# schema_v2_2.net
KiCad netlist of a schematic drawn in EAGLE
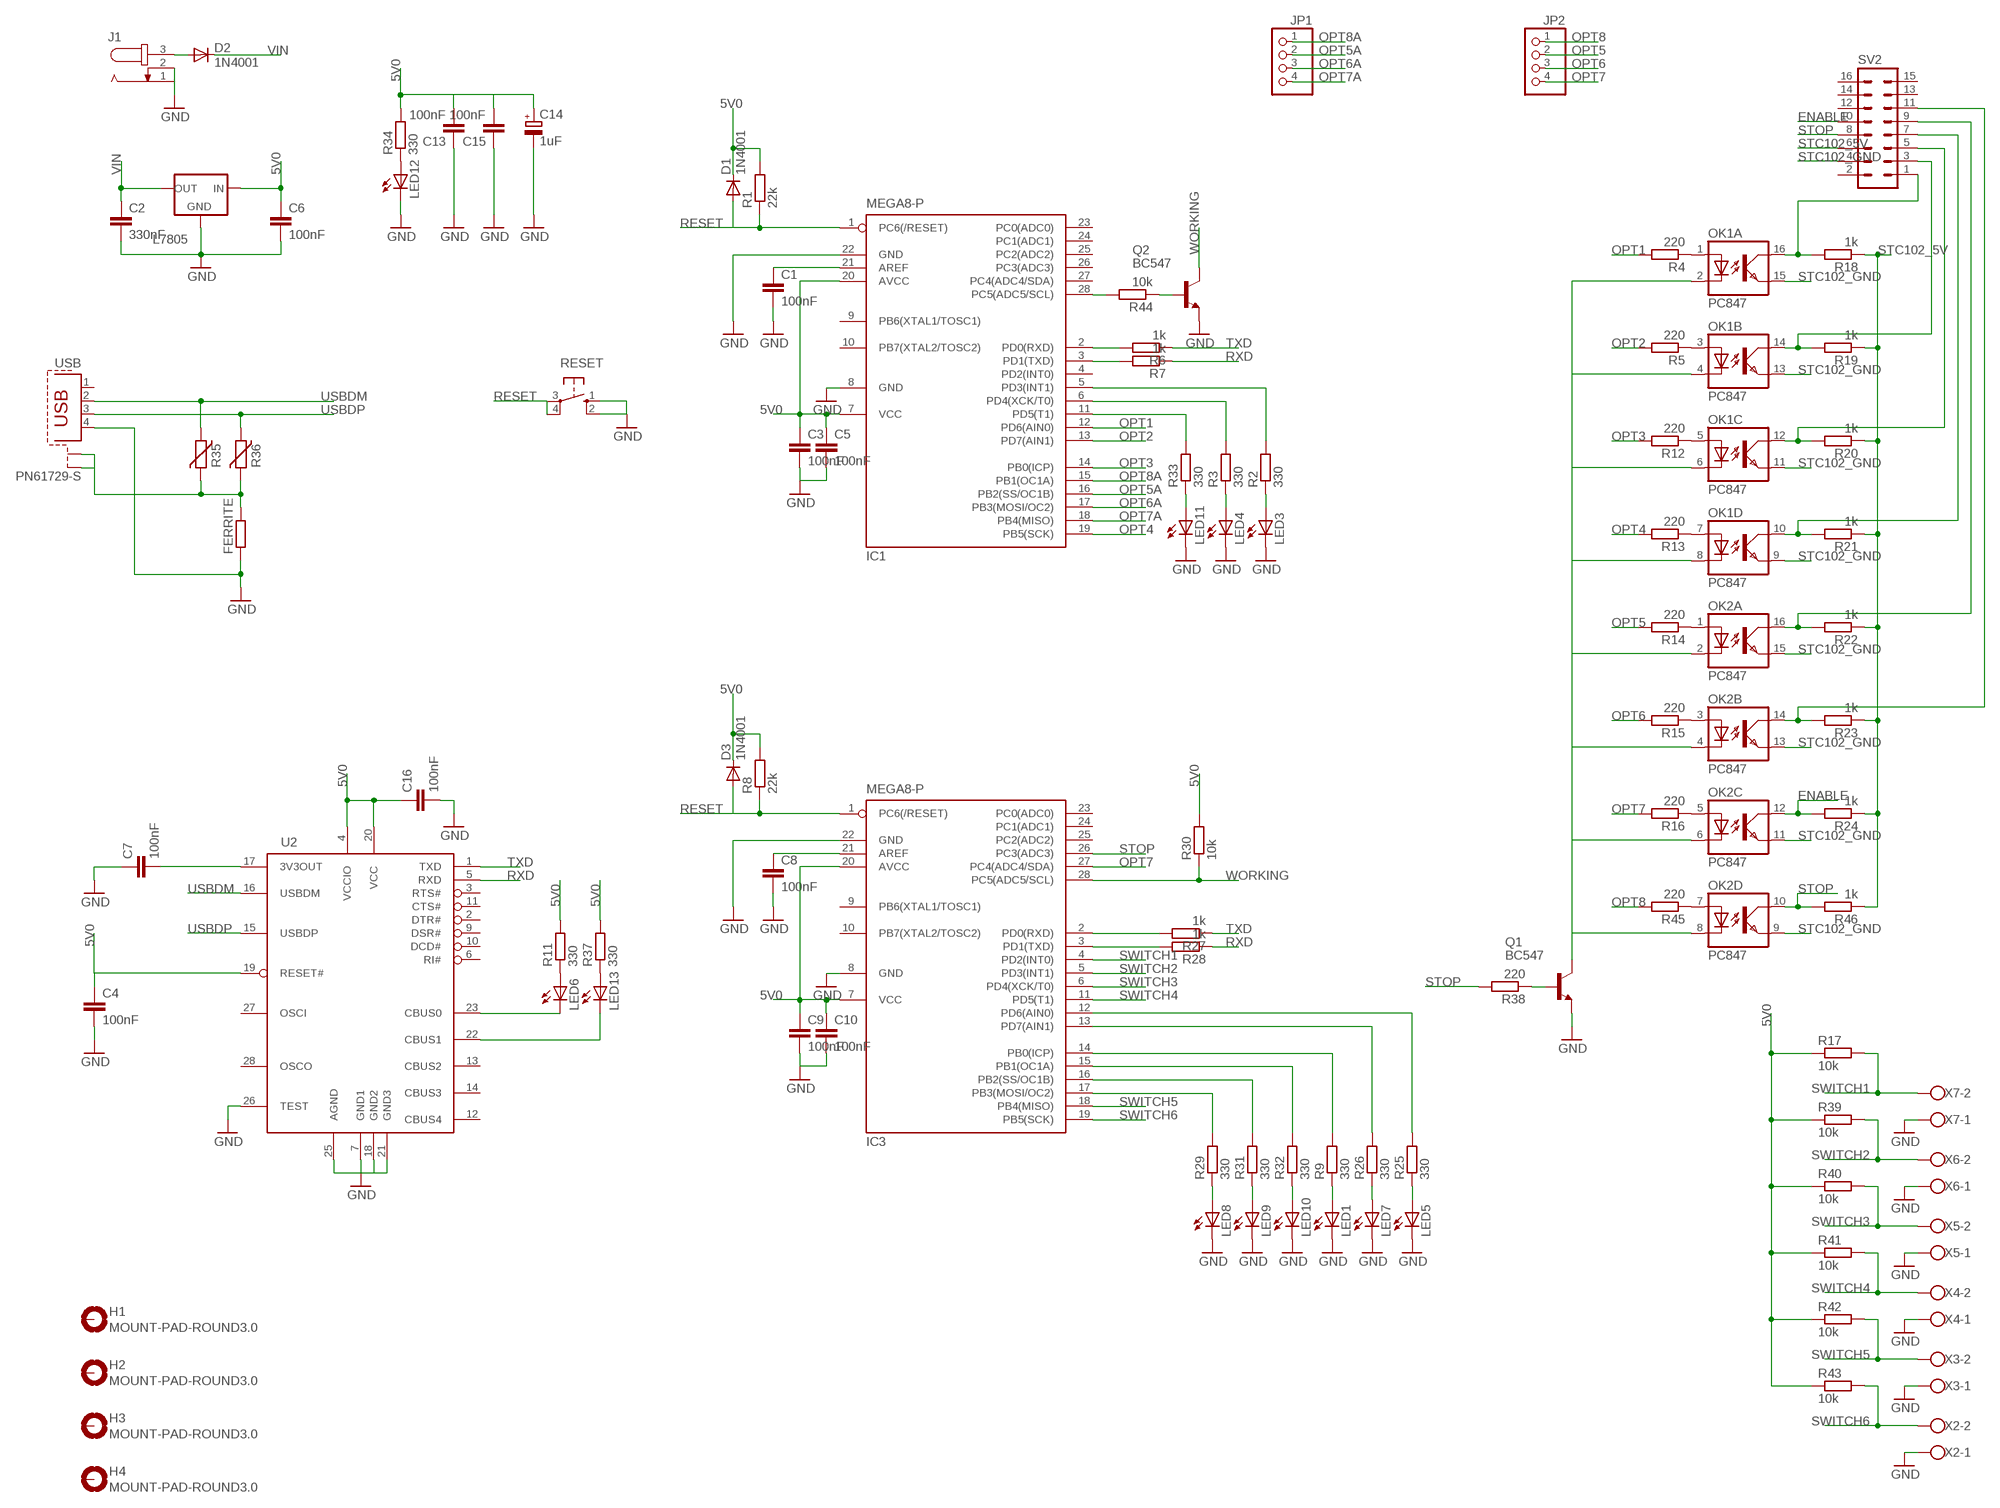
[diagram p0: schematic, sheet 1]

(export (version "E")
  (design (tool "Eeschema 10.0.6"))
  (components
    (comp (ref "C1")
      (value "100nF")
      (footprint "eagle-import:C0805")
      (libsource (lib "eagle-import") (part "C-EUC0805"))
    )
    (comp (ref "C2")
      (value "330nF")
      (footprint "eagle-import:C025-025X050")
      (libsource (lib "eagle-import") (part "C-EU025-025X050"))
    )
    (comp (ref "C3")
      (value "100nF")
      (footprint "eagle-import:C025-025X050")
      (libsource (lib "eagle-import") (part "C-EU025-025X050"))
    )
    (comp (ref "C4")
      (value "100nF")
      (footprint "eagle-import:C0603K")
      (libsource (lib "eagle-import") (part "C-EUC0603K"))
    )
    (comp (ref "C5")
      (value "100nF")
      (footprint "eagle-import:C025-025X050")
      (libsource (lib "eagle-import") (part "C-EU025-025X050"))
    )
    (comp (ref "C6")
      (value "100nF")
      (footprint "eagle-import:C025-025X050")
      (libsource (lib "eagle-import") (part "C-EU025-025X050"))
    )
    (comp (ref "C7")
      (value "100nF")
      (footprint "eagle-import:C0603K")
      (libsource (lib "eagle-import") (part "C-EUC0603K"))
    )
    (comp (ref "C8")
      (value "100nF")
      (footprint "eagle-import:C025-025X050")
      (libsource (lib "eagle-import") (part "C-EU025-025X050"))
    )
    (comp (ref "C9")
      (value "100nF")
      (footprint "eagle-import:C025-025X050")
      (libsource (lib "eagle-import") (part "C-EU025-025X050"))
    )
    (comp (ref "C10")
      (value "100nF")
      (footprint "eagle-import:C025-025X050")
      (libsource (lib "eagle-import") (part "C-EU025-025X050"))
    )
    (comp (ref "C13")
      (value "100nF")
      (footprint "eagle-import:C025-025X050")
      (libsource (lib "eagle-import") (part "C-EU025-025X050"))
    )
    (comp (ref "C14")
      (value "1uF")
      (footprint "eagle-import:E2,5-5")
      (libsource (lib "eagle-import") (part "CPOL-EUE2.5-5"))
    )
    (comp (ref "C15")
      (value "100nF")
      (footprint "eagle-import:C025-025X050")
      (libsource (lib "eagle-import") (part "C-EU025-025X050"))
    )
    (comp (ref "C16")
      (value "100nF")
      (footprint "eagle-import:C0603K")
      (libsource (lib "eagle-import") (part "C-EUC0603K"))
    )
    (comp (ref "D1")
      (value "1N4001")
      (footprint "eagle-import:DO41-10")
      (libsource (lib "eagle-import") (part "1N4004"))
    )
    (comp (ref "D2")
      (value "1N4001")
      (footprint "eagle-import:DO41-10")
      (libsource (lib "eagle-import") (part "1N4004"))
    )
    (comp (ref "D3")
      (value "1N4001")
      (footprint "eagle-import:DO41-10")
      (libsource (lib "eagle-import") (part "1N4004"))
    )
    (comp (ref "FERRITE")
      (value "R-EU_M0805")
      (footprint "eagle-import:M0805")
      (libsource (lib "eagle-import") (part "resistor_R-EU_M0805"))
    )
    (comp (ref "H1")
      (value "MOUNT-PAD-ROUND3.0")
      (footprint "eagle-import:3,0-PAD")
      (libsource (lib "eagle-import") (part "MOUNT-PAD-ROUND3.0"))
    )
    (comp (ref "H2")
      (value "MOUNT-PAD-ROUND3.0")
      (footprint "eagle-import:3,0-PAD")
      (libsource (lib "eagle-import") (part "MOUNT-PAD-ROUND3.0"))
    )
    (comp (ref "H3")
      (value "MOUNT-PAD-ROUND3.0")
      (footprint "eagle-import:3,0-PAD")
      (libsource (lib "eagle-import") (part "MOUNT-PAD-ROUND3.0"))
    )
    (comp (ref "H4")
      (value "MOUNT-PAD-ROUND3.0")
      (footprint "eagle-import:3,0-PAD")
      (libsource (lib "eagle-import") (part "MOUNT-PAD-ROUND3.0"))
    )
    (comp (ref "IC1")
      (value "MEGA8-P")
      (footprint "eagle-import:DIL28-3")
      (libsource (lib "eagle-import") (part "MEGA8-P"))
    )
    (comp (ref "IC3")
      (value "MEGA8-P")
      (footprint "eagle-import:DIL28-3")
      (libsource (lib "eagle-import") (part "MEGA8-P"))
    )
    (comp (ref "J1")
      (value "JACK-PLUG0")
      (footprint "eagle-import:SPC4077")
      (libsource (lib "eagle-import") (part "JACK-PLUG0"))
    )
    (comp (ref "JP1")
      (value "PINHD-1X4")
      (footprint "eagle-import:1X04")
      (libsource (lib "eagle-import") (part "PINHD-1X4"))
    )
    (comp (ref "JP2")
      (value "PINHD-1X4")
      (footprint "eagle-import:1X04")
      (libsource (lib "eagle-import") (part "PINHD-1X4"))
    )
    (comp (ref "L7805")
      (value "79XXS")
      (footprint "eagle-import:79XXS")
      (libsource (lib "eagle-import") (part "79XXS"))
    )
    (comp (ref "LED1")
      (value "LED3MM")
      (footprint "eagle-import:LED3MM")
      (libsource (lib "eagle-import") (part "LED3MM"))
    )
    (comp (ref "LED3")
      (value "LED3MM")
      (footprint "eagle-import:LED3MM")
      (libsource (lib "eagle-import") (part "LED3MM"))
    )
    (comp (ref "LED4")
      (value "LED3MM")
      (footprint "eagle-import:LED3MM")
      (libsource (lib "eagle-import") (part "LED3MM"))
    )
    (comp (ref "LED5")
      (value "LED3MM")
      (footprint "eagle-import:LED3MM")
      (libsource (lib "eagle-import") (part "LED3MM"))
    )
    (comp (ref "LED6")
      (value "LED3MM")
      (footprint "eagle-import:LED3MM")
      (libsource (lib "eagle-import") (part "LED3MM"))
    )
    (comp (ref "LED7")
      (value "LED3MM")
      (footprint "eagle-import:LED3MM")
      (libsource (lib "eagle-import") (part "LED3MM"))
    )
    (comp (ref "LED8")
      (value "LED3MM")
      (footprint "eagle-import:LED3MM")
      (libsource (lib "eagle-import") (part "LED3MM"))
    )
    (comp (ref "LED9")
      (value "LED3MM")
      (footprint "eagle-import:LED3MM")
      (libsource (lib "eagle-import") (part "LED3MM"))
    )
    (comp (ref "LED10")
      (value "LED3MM")
      (footprint "eagle-import:LED3MM")
      (libsource (lib "eagle-import") (part "LED3MM"))
    )
    (comp (ref "LED11")
      (value "LED3MM")
      (footprint "eagle-import:LED3MM")
      (libsource (lib "eagle-import") (part "LED3MM"))
    )
    (comp (ref "LED12")
      (value "LED3MM")
      (footprint "eagle-import:LED3MM")
      (libsource (lib "eagle-import") (part "LED3MM"))
    )
    (comp (ref "LED13")
      (value "LED3MM")
      (footprint "eagle-import:LED3MM")
      (libsource (lib "eagle-import") (part "LED3MM"))
    )
    (comp (ref "OK1")
      (value "PC847")
      (footprint "eagle-import:DIL16")
      (libsource (lib "eagle-import") (part "PC847"))
    )
    (comp (ref "OK2")
      (value "PC847")
      (footprint "eagle-import:DIL16")
      (libsource (lib "eagle-import") (part "PC847"))
    )
    (comp (ref "Q1")
      (value "BC547")
      (footprint "eagle-import:TO92")
      (libsource (lib "eagle-import") (part "BC547"))
    )
    (comp (ref "Q2")
      (value "BC547")
      (footprint "eagle-import:TO92")
      (libsource (lib "eagle-import") (part "BC547"))
    )
    (comp (ref "R1")
      (value "22k")
      (footprint "eagle-import:0207_10")
      (libsource (lib "eagle-import") (part "R-EU_0207/10"))
    )
    (comp (ref "R2")
      (value "330")
      (footprint "eagle-import:0207_10")
      (libsource (lib "eagle-import") (part "R-EU_0207/10"))
    )
    (comp (ref "R3")
      (value "330")
      (footprint "eagle-import:0207_10")
      (libsource (lib "eagle-import") (part "R-EU_0207/10"))
    )
    (comp (ref "R4")
      (value "220")
      (footprint "eagle-import:0207_10")
      (libsource (lib "eagle-import") (part "R-EU_0207/10"))
    )
    (comp (ref "R5")
      (value "220")
      (footprint "eagle-import:0207_10")
      (libsource (lib "eagle-import") (part "R-EU_0207/10"))
    )
    (comp (ref "R6")
      (value "1k")
      (footprint "eagle-import:0207_10")
      (libsource (lib "eagle-import") (part "R-EU_0207/10"))
    )
    (comp (ref "R7")
      (value "1k")
      (footprint "eagle-import:0207_10")
      (libsource (lib "eagle-import") (part "R-EU_0207/10"))
    )
    (comp (ref "R8")
      (value "22k")
      (footprint "eagle-import:0207_10")
      (libsource (lib "eagle-import") (part "R-EU_0207/10"))
    )
    (comp (ref "R9")
      (value "330")
      (footprint "eagle-import:0207_10")
      (libsource (lib "eagle-import") (part "R-EU_0207/10"))
    )
    (comp (ref "R11")
      (value "330")
      (footprint "eagle-import:0207_10")
      (libsource (lib "eagle-import") (part "R-EU_0207/10"))
    )
    (comp (ref "R12")
      (value "220")
      (footprint "eagle-import:0207_10")
      (libsource (lib "eagle-import") (part "R-EU_0207/10"))
    )
    (comp (ref "R13")
      (value "220")
      (footprint "eagle-import:0207_10")
      (libsource (lib "eagle-import") (part "R-EU_0207/10"))
    )
    (comp (ref "R14")
      (value "220")
      (footprint "eagle-import:0207_10")
      (libsource (lib "eagle-import") (part "R-EU_0207/10"))
    )
    (comp (ref "R15")
      (value "220")
      (footprint "eagle-import:0207_10")
      (libsource (lib "eagle-import") (part "R-EU_0207/10"))
    )
    (comp (ref "R16")
      (value "220")
      (footprint "eagle-import:0207_10")
      (libsource (lib "eagle-import") (part "R-EU_0207/10"))
    )
    (comp (ref "R17")
      (value "10k")
      (footprint "eagle-import:0207_10")
      (libsource (lib "eagle-import") (part "R-EU_0207/10"))
    )
    (comp (ref "R18")
      (value "1k")
      (footprint "eagle-import:0207_10")
      (libsource (lib "eagle-import") (part "R-EU_0207/10"))
    )
    (comp (ref "R19")
      (value "1k")
      (footprint "eagle-import:0207_10")
      (libsource (lib "eagle-import") (part "R-EU_0207/10"))
    )
    (comp (ref "R20")
      (value "1k")
      (footprint "eagle-import:0207_10")
      (libsource (lib "eagle-import") (part "R-EU_0207/10"))
    )
    (comp (ref "R21")
      (value "1k")
      (footprint "eagle-import:0207_10")
      (libsource (lib "eagle-import") (part "R-EU_0207/10"))
    )
    (comp (ref "R22")
      (value "1k")
      (footprint "eagle-import:0207_10")
      (libsource (lib "eagle-import") (part "R-EU_0207/10"))
    )
    (comp (ref "R23")
      (value "1k")
      (footprint "eagle-import:0207_10")
      (libsource (lib "eagle-import") (part "R-EU_0207/10"))
    )
    (comp (ref "R24")
      (value "1k")
      (footprint "eagle-import:0207_10")
      (libsource (lib "eagle-import") (part "R-EU_0207/10"))
    )
    (comp (ref "R25")
      (value "330")
      (footprint "eagle-import:0207_10")
      (libsource (lib "eagle-import") (part "R-EU_0207/10"))
    )
    (comp (ref "R26")
      (value "330")
      (footprint "eagle-import:0207_10")
      (libsource (lib "eagle-import") (part "R-EU_0207/10"))
    )
    (comp (ref "R27")
      (value "1k")
      (footprint "eagle-import:0207_10")
      (libsource (lib "eagle-import") (part "R-EU_0207/10"))
    )
    (comp (ref "R28")
      (value "1k")
      (footprint "eagle-import:0207_10")
      (libsource (lib "eagle-import") (part "R-EU_0207/10"))
    )
    (comp (ref "R29")
      (value "330")
      (footprint "eagle-import:0207_10")
      (libsource (lib "eagle-import") (part "R-EU_0207/10"))
    )
    (comp (ref "R30")
      (value "10k")
      (footprint "eagle-import:0207_10")
      (libsource (lib "eagle-import") (part "R-EU_0207/10"))
    )
    (comp (ref "R31")
      (value "330")
      (footprint "eagle-import:0207_10")
      (libsource (lib "eagle-import") (part "R-EU_0207/10"))
    )
    (comp (ref "R32")
      (value "330")
      (footprint "eagle-import:0207_10")
      (libsource (lib "eagle-import") (part "R-EU_0207/10"))
    )
    (comp (ref "R33")
      (value "330")
      (footprint "eagle-import:0207_10")
      (libsource (lib "eagle-import") (part "R-EU_0207/10"))
    )
    (comp (ref "R34")
      (value "330")
      (footprint "eagle-import:0207_10")
      (libsource (lib "eagle-import") (part "R-EU_0207/10"))
    )
    (comp (ref "R35")
      (value "VARISTORCN0603")
      (footprint "eagle-import:CT_CN0603")
      (libsource (lib "eagle-import") (part "VARISTORCN0603"))
    )
    (comp (ref "R36")
      (value "VARISTORCN0603")
      (footprint "eagle-import:CT_CN0603")
      (libsource (lib "eagle-import") (part "VARISTORCN0603"))
    )
    (comp (ref "R37")
      (value "330")
      (footprint "eagle-import:0207_10")
      (libsource (lib "eagle-import") (part "R-EU_0207/10"))
    )
    (comp (ref "R38")
      (value "220")
      (footprint "eagle-import:0207_10")
      (libsource (lib "eagle-import") (part "R-EU_0207/10"))
    )
    (comp (ref "R39")
      (value "10k")
      (footprint "eagle-import:0207_10")
      (libsource (lib "eagle-import") (part "R-EU_0207/10"))
    )
    (comp (ref "R40")
      (value "10k")
      (footprint "eagle-import:0207_10")
      (libsource (lib "eagle-import") (part "R-EU_0207/10"))
    )
    (comp (ref "R41")
      (value "10k")
      (footprint "eagle-import:0207_10")
      (libsource (lib "eagle-import") (part "R-EU_0207/10"))
    )
    (comp (ref "R42")
      (value "10k")
      (footprint "eagle-import:0207_10")
      (libsource (lib "eagle-import") (part "R-EU_0207/10"))
    )
    (comp (ref "R43")
      (value "10k")
      (footprint "eagle-import:0207_10")
      (libsource (lib "eagle-import") (part "R-EU_0207/10"))
    )
    (comp (ref "R44")
      (value "10k")
      (footprint "eagle-import:0207_10")
      (libsource (lib "eagle-import") (part "R-EU_0207/10"))
    )
    (comp (ref "R45")
      (value "220")
      (footprint "eagle-import:0207_10")
      (libsource (lib "eagle-import") (part "R-EU_0207/10"))
    )
    (comp (ref "R46")
      (value "1k")
      (footprint "eagle-import:0207_10")
      (libsource (lib "eagle-import") (part "R-EU_0207/10"))
    )
    (comp (ref "RESET")
      (value "10-XX")
      (footprint "eagle-import:B3F-10XX")
      (fields (field (name "MPN") "B3F-1000"))
      (libsource (lib "eagle-import") (part "10-XX"))
    )
    (comp (ref "SV2")
      (value "MA08-2")
      (footprint "eagle-import:MA08-2")
      (libsource (lib "eagle-import") (part "MA08-2"))
    )
    (comp (ref "U2")
      (value "FT232RL")
      (footprint "eagle-import:SSOP28DB")
      (libsource (lib "eagle-import") (part "FT232RL"))
    )
    (comp (ref "USB")
      (value "PN61729-S")
      (footprint "eagle-import:PN61729-S")
      (fields (field (name "OC_FARNELL") "unknown") (field (name "OC_NEWARK") "unknown"))
      (libsource (lib "eagle-import") (part "PN61729-S"))
    )
    (comp (ref "X2")
      (value "W237-102")
      (footprint "eagle-import:W237-102")
      (fields (field (name "MPN") "237-102"))
      (libsource (lib "eagle-import") (part "W237-102"))
    )
    (comp (ref "X3")
      (value "W237-102")
      (footprint "eagle-import:W237-102")
      (fields (field (name "MPN") "237-102"))
      (libsource (lib "eagle-import") (part "W237-102"))
    )
    (comp (ref "X4")
      (value "W237-102")
      (footprint "eagle-import:W237-102")
      (fields (field (name "MPN") "237-102"))
      (libsource (lib "eagle-import") (part "W237-102"))
    )
    (comp (ref "X5")
      (value "W237-102")
      (footprint "eagle-import:W237-102")
      (fields (field (name "MPN") "237-102"))
      (libsource (lib "eagle-import") (part "W237-102"))
    )
    (comp (ref "X6")
      (value "W237-102")
      (footprint "eagle-import:W237-102")
      (fields (field (name "MPN") "237-102"))
      (libsource (lib "eagle-import") (part "W237-102"))
    )
    (comp (ref "X7")
      (value "W237-102")
      (footprint "eagle-import:W237-102")
      (fields (field (name "MPN") "237-102"))
      (libsource (lib "eagle-import") (part "W237-102"))
    )
  )
  (nets
    (net (code "1") (name "/5V0") (class "Default")
      (node (ref "C10") (pin "1") (pinfunction "1_1") (pintype "passive"))
      (node (ref "C13") (pin "2") (pinfunction "2_2") (pintype "passive"))
      (node (ref "C14") (pin "+") (pinfunction "+_+") (pintype "passive"))
      (node (ref "C15") (pin "2") (pinfunction "2_2") (pintype "passive"))
      (node (ref "C16") (pin "1") (pinfunction "1_1") (pintype "passive"))
      (node (ref "C3") (pin "1") (pinfunction "1_1") (pintype "passive"))
      (node (ref "C4") (pin "1") (pinfunction "1_1") (pintype "passive"))
      (node (ref "C5") (pin "1") (pinfunction "1_1") (pintype "passive"))
      (node (ref "C6") (pin "1") (pinfunction "1_1") (pintype "passive"))
      (node (ref "C9") (pin "1") (pinfunction "1_1") (pintype "passive"))
      (node (ref "D1") (pin "C") (pinfunction "C_C") (pintype "passive"))
      (node (ref "D3") (pin "C") (pinfunction "C_C") (pintype "passive"))
      (node (ref "IC1") (pin "20") (pinfunction "AVCC_20") (pintype "power_in"))
      (node (ref "IC1") (pin "7") (pinfunction "VCC_7") (pintype "power_in"))
      (node (ref "IC3") (pin "20") (pinfunction "AVCC_20") (pintype "power_in"))
      (node (ref "IC3") (pin "7") (pinfunction "VCC_7") (pintype "power_in"))
      (node (ref "L7805") (pin "IN") (pinfunction "IN_IN") (pintype "input"))
      (node (ref "R1") (pin "2") (pinfunction "2_2") (pintype "passive"))
      (node (ref "R11") (pin "2") (pinfunction "2_2") (pintype "passive"))
      (node (ref "R17") (pin "1") (pinfunction "1_1") (pintype "passive"))
      (node (ref "R30") (pin "2") (pinfunction "2_2") (pintype "passive"))
      (node (ref "R34") (pin "2") (pinfunction "2_2") (pintype "passive"))
      (node (ref "R37") (pin "2") (pinfunction "2_2") (pintype "passive"))
      (node (ref "R39") (pin "1") (pinfunction "1_1") (pintype "passive"))
      (node (ref "R40") (pin "1") (pinfunction "1_1") (pintype "passive"))
      (node (ref "R41") (pin "1") (pinfunction "1_1") (pintype "passive"))
      (node (ref "R42") (pin "1") (pinfunction "1_1") (pintype "passive"))
      (node (ref "R43") (pin "1") (pinfunction "1_1") (pintype "passive"))
      (node (ref "R8") (pin "2") (pinfunction "2_2") (pintype "passive"))
      (node (ref "U2") (pin "19") (pinfunction "RESET#_19") (pintype "input"))
      (node (ref "U2") (pin "20") (pinfunction "VCC_20") (pintype "power_in"))
      (node (ref "U2") (pin "4") (pinfunction "VCCIO_4") (pintype "power_in"))
    )
    (net (code "2") (name "/ENABLE") (class "Default")
      (node (ref "OK2") (pin "12") (pinfunction "COL_12") (pintype "passive"))
      (node (ref "R24") (pin "2") (pinfunction "2_2") (pintype "passive"))
      (node (ref "SV2") (pin "10") (pinfunction "10_10") (pintype "passive"))
    )
    (net (code "3") (name "/OPT1") (class "Default")
      (node (ref "IC1") (pin "12") (pinfunction "PD6(AIN0)_12") (pintype "bidirectional"))
      (node (ref "R4") (pin "2") (pinfunction "2_2") (pintype "passive"))
    )
    (net (code "4") (name "/OPT2") (class "Default")
      (node (ref "IC1") (pin "13") (pinfunction "PD7(AIN1)_13") (pintype "bidirectional"))
      (node (ref "R5") (pin "2") (pinfunction "2_2") (pintype "passive"))
    )
    (net (code "5") (name "/OPT3") (class "Default")
      (node (ref "IC1") (pin "14") (pinfunction "PB0(ICP)_14") (pintype "bidirectional"))
      (node (ref "R12") (pin "2") (pinfunction "2_2") (pintype "passive"))
    )
    (net (code "6") (name "/OPT4") (class "Default")
      (node (ref "IC1") (pin "19") (pinfunction "PB5(SCK)_19") (pintype "bidirectional"))
      (node (ref "R13") (pin "2") (pinfunction "2_2") (pintype "passive"))
    )
    (net (code "7") (name "/OPT5") (class "Default")
      (node (ref "JP2") (pin "2") (pinfunction "2_2") (pintype "passive"))
      (node (ref "R14") (pin "2") (pinfunction "2_2") (pintype "passive"))
    )
    (net (code "8") (name "/OPT5A") (class "Default")
      (node (ref "IC1") (pin "16") (pinfunction "PB2(SS/OC1B)_16") (pintype "bidirectional"))
      (node (ref "JP1") (pin "2") (pinfunction "2_2") (pintype "passive"))
    )
    (net (code "9") (name "/OPT6") (class "Default")
      (node (ref "JP2") (pin "3") (pinfunction "3_3") (pintype "passive"))
      (node (ref "R15") (pin "2") (pinfunction "2_2") (pintype "passive"))
    )
    (net (code "10") (name "/OPT6A") (class "Default")
      (node (ref "IC1") (pin "17") (pinfunction "PB3(MOSI/OC2)_17") (pintype "bidirectional"))
      (node (ref "JP1") (pin "3") (pinfunction "3_3") (pintype "passive"))
    )
    (net (code "11") (name "/OPT7") (class "Default")
      (node (ref "IC3") (pin "27") (pinfunction "PC4(ADC4/SDA)_27") (pintype "bidirectional"))
      (node (ref "JP2") (pin "4") (pinfunction "4_4") (pintype "passive"))
      (node (ref "R16") (pin "2") (pinfunction "2_2") (pintype "passive"))
    )
    (net (code "12") (name "/OPT7A") (class "Default")
      (node (ref "IC1") (pin "18") (pinfunction "PB4(MISO)_18") (pintype "bidirectional"))
      (node (ref "JP1") (pin "4") (pinfunction "4_4") (pintype "passive"))
    )
    (net (code "13") (name "/OPT8") (class "Default")
      (node (ref "JP2") (pin "1") (pinfunction "1_1") (pintype "passive"))
      (node (ref "R45") (pin "2") (pinfunction "2_2") (pintype "passive"))
    )
    (net (code "14") (name "/OPT8A") (class "Default")
      (node (ref "IC1") (pin "15") (pinfunction "PB1(OC1A)_15") (pintype "bidirectional"))
      (node (ref "JP1") (pin "1") (pinfunction "1_1") (pintype "passive"))
    )
    (net (code "15") (name "/RESET") (class "Default")
      (node (ref "D1") (pin "A") (pinfunction "A_A") (pintype "passive"))
      (node (ref "D3") (pin "A") (pinfunction "A_A") (pintype "passive"))
      (node (ref "IC1") (pin "1") (pinfunction "PC6(/RESET)_1") (pintype "bidirectional"))
      (node (ref "IC3") (pin "1") (pinfunction "PC6(/RESET)_1") (pintype "bidirectional"))
      (node (ref "R1") (pin "1") (pinfunction "1_1") (pintype "passive"))
      (node (ref "R8") (pin "1") (pinfunction "1_1") (pintype "passive"))
      (node (ref "RESET") (pin "3") (pinfunction "P_3") (pintype "passive"))
      (node (ref "RESET") (pin "4") (pinfunction "P1_4") (pintype "passive"))
    )
    (net (code "16") (name "/RXD") (class "Default")
      (node (ref "R28") (pin "1") (pinfunction "1_1") (pintype "passive"))
      (node (ref "R7") (pin "1") (pinfunction "1_1") (pintype "passive"))
      (node (ref "U2") (pin "5") (pinfunction "RXD_5") (pintype "input"))
    )
    (net (code "17") (name "/STC102_5V") (class "Default")
      (node (ref "R18") (pin "1") (pinfunction "1_1") (pintype "passive"))
      (node (ref "R19") (pin "1") (pinfunction "1_1") (pintype "passive"))
      (node (ref "R20") (pin "1") (pinfunction "1_1") (pintype "passive"))
      (node (ref "R21") (pin "1") (pinfunction "1_1") (pintype "passive"))
      (node (ref "R22") (pin "1") (pinfunction "1_1") (pintype "passive"))
      (node (ref "R23") (pin "1") (pinfunction "1_1") (pintype "passive"))
      (node (ref "R24") (pin "1") (pinfunction "1_1") (pintype "passive"))
      (node (ref "R46") (pin "1") (pinfunction "1_1") (pintype "passive"))
      (node (ref "SV2") (pin "6") (pinfunction "6_6") (pintype "passive"))
    )
    (net (code "18") (name "/STC102_GND") (class "Default")
      (node (ref "OK1") (pin "11") (pinfunction "EMIT_11") (pintype "passive"))
      (node (ref "OK1") (pin "13") (pinfunction "EMIT_13") (pintype "passive"))
      (node (ref "OK1") (pin "15") (pinfunction "EMIT_15") (pintype "passive"))
      (node (ref "OK1") (pin "9") (pinfunction "EMIT_9") (pintype "passive"))
      (node (ref "OK2") (pin "11") (pinfunction "EMIT_11") (pintype "passive"))
      (node (ref "OK2") (pin "13") (pinfunction "EMIT_13") (pintype "passive"))
      (node (ref "OK2") (pin "15") (pinfunction "EMIT_15") (pintype "passive"))
      (node (ref "OK2") (pin "9") (pinfunction "EMIT_9") (pintype "passive"))
      (node (ref "SV2") (pin "4") (pinfunction "4_4") (pintype "passive"))
    )
    (net (code "19") (name "/STOP") (class "Default")
      (node (ref "IC3") (pin "26") (pinfunction "PC3(ADC3)_26") (pintype "bidirectional"))
      (node (ref "OK2") (pin "10") (pinfunction "COL_10") (pintype "passive"))
      (node (ref "R38") (pin "2") (pinfunction "2_2") (pintype "passive"))
      (node (ref "R46") (pin "2") (pinfunction "2_2") (pintype "passive"))
      (node (ref "SV2") (pin "8") (pinfunction "8_8") (pintype "passive"))
    )
    (net (code "20") (name "/SWITCH1") (class "Default")
      (node (ref "IC3") (pin "4") (pinfunction "PD2(INT0)_4") (pintype "bidirectional"))
      (node (ref "R17") (pin "2") (pinfunction "2_2") (pintype "passive"))
      (node (ref "X7") (pin "2") (pinfunction "KL_2") (pintype "passive"))
    )
    (net (code "21") (name "/SWITCH2") (class "Default")
      (node (ref "IC3") (pin "5") (pinfunction "PD3(INT1)_5") (pintype "bidirectional"))
      (node (ref "R39") (pin "2") (pinfunction "2_2") (pintype "passive"))
      (node (ref "X6") (pin "2") (pinfunction "KL_2") (pintype "passive"))
    )
    (net (code "22") (name "/SWITCH3") (class "Default")
      (node (ref "IC3") (pin "6") (pinfunction "PD4(XCK/T0)_6") (pintype "bidirectional"))
      (node (ref "R40") (pin "2") (pinfunction "2_2") (pintype "passive"))
      (node (ref "X5") (pin "2") (pinfunction "KL_2") (pintype "passive"))
    )
    (net (code "23") (name "/SWITCH4") (class "Default")
      (node (ref "IC3") (pin "11") (pinfunction "PD5(T1)_11") (pintype "bidirectional"))
      (node (ref "R41") (pin "2") (pinfunction "2_2") (pintype "passive"))
      (node (ref "X4") (pin "2") (pinfunction "KL_2") (pintype "passive"))
    )
    (net (code "24") (name "/SWITCH5") (class "Default")
      (node (ref "IC3") (pin "18") (pinfunction "PB4(MISO)_18") (pintype "bidirectional"))
      (node (ref "R42") (pin "2") (pinfunction "2_2") (pintype "passive"))
      (node (ref "X3") (pin "2") (pinfunction "KL_2") (pintype "passive"))
    )
    (net (code "25") (name "/SWITCH6") (class "Default")
      (node (ref "IC3") (pin "19") (pinfunction "PB5(SCK)_19") (pintype "bidirectional"))
      (node (ref "R43") (pin "2") (pinfunction "2_2") (pintype "passive"))
      (node (ref "X2") (pin "2") (pinfunction "KL_2") (pintype "passive"))
    )
    (net (code "26") (name "/TXD") (class "Default")
      (node (ref "R27") (pin "1") (pinfunction "1_1") (pintype "passive"))
      (node (ref "R6") (pin "1") (pinfunction "1_1") (pintype "passive"))
      (node (ref "U2") (pin "1") (pinfunction "TXD_1") (pintype "output"))
    )
    (net (code "27") (name "/USBDM") (class "Default")
      (node (ref "R35") (pin "1") (pinfunction "1_1") (pintype "passive"))
      (node (ref "U2") (pin "16") (pinfunction "USBDM_16") (pintype "bidirectional"))
      (node (ref "USB") (pin "2") (pinfunction "2_2") (pintype "passive"))
    )
    (net (code "28") (name "/USBDP") (class "Default")
      (node (ref "R36") (pin "1") (pinfunction "1_1") (pintype "passive"))
      (node (ref "U2") (pin "15") (pinfunction "USBDP_15") (pintype "bidirectional"))
      (node (ref "USB") (pin "3") (pinfunction "3_3") (pintype "passive"))
    )
    (net (code "29") (name "/VIN") (class "Default")
      (node (ref "C2") (pin "1") (pinfunction "1_1") (pintype "passive"))
      (node (ref "D2") (pin "C") (pinfunction "C_C") (pintype "passive"))
      (node (ref "L7805") (pin "OUT") (pinfunction "OUT_OUT") (pintype "passive"))
    )
    (net (code "30") (name "/WORKING") (class "Default")
      (node (ref "IC3") (pin "28") (pinfunction "PC5(ADC5/SCL)_28") (pintype "bidirectional"))
      (node (ref "Q2") (pin "3") (pinfunction "C_3") (pintype "passive"))
      (node (ref "R30") (pin "1") (pinfunction "1_1") (pintype "passive"))
    )
    (net (code "31") (name "GND") (class "Default")
      (node (ref "C1") (pin "2") (pinfunction "2_2") (pintype "passive"))
      (node (ref "C10") (pin "2") (pinfunction "2_2") (pintype "passive"))
      (node (ref "C13") (pin "1") (pinfunction "1_1") (pintype "passive"))
      (node (ref "C14") (pin "-") (pinfunction "-_-") (pintype "passive"))
      (node (ref "C15") (pin "1") (pinfunction "1_1") (pintype "passive"))
      (node (ref "C16") (pin "2") (pinfunction "2_2") (pintype "passive"))
      (node (ref "C2") (pin "2") (pinfunction "2_2") (pintype "passive"))
      (node (ref "C3") (pin "2") (pinfunction "2_2") (pintype "passive"))
      (node (ref "C4") (pin "2") (pinfunction "2_2") (pintype "passive"))
      (node (ref "C5") (pin "2") (pinfunction "2_2") (pintype "passive"))
      (node (ref "C6") (pin "2") (pinfunction "2_2") (pintype "passive"))
      (node (ref "C7") (pin "1") (pinfunction "1_1") (pintype "passive"))
      (node (ref "C8") (pin "2") (pinfunction "2_2") (pintype "passive"))
      (node (ref "C9") (pin "2") (pinfunction "2_2") (pintype "passive"))
      (node (ref "FERRITE") (pin "1") (pinfunction "1_1") (pintype "passive"))
      (node (ref "IC1") (pin "22") (pinfunction "GND_22") (pintype "power_in"))
      (node (ref "IC1") (pin "8") (pinfunction "GND_8") (pintype "power_in"))
      (node (ref "IC3") (pin "22") (pinfunction "GND_22") (pintype "power_in"))
      (node (ref "IC3") (pin "8") (pinfunction "GND_8") (pintype "power_in"))
      (node (ref "J1") (pin "1") (pinfunction "1_1") (pintype "passive"))
      (node (ref "J1") (pin "2") (pinfunction "2_2") (pintype "passive"))
      (node (ref "L7805") (pin "GND") (pinfunction "GND_GND") (pintype "input"))
      (node (ref "LED1") (pin "K") (pinfunction "C_K") (pintype "passive"))
      (node (ref "LED10") (pin "K") (pinfunction "C_K") (pintype "passive"))
      (node (ref "LED11") (pin "K") (pinfunction "C_K") (pintype "passive"))
      (node (ref "LED12") (pin "K") (pinfunction "C_K") (pintype "passive"))
      (node (ref "LED3") (pin "K") (pinfunction "C_K") (pintype "passive"))
      (node (ref "LED4") (pin "K") (pinfunction "C_K") (pintype "passive"))
      (node (ref "LED5") (pin "K") (pinfunction "C_K") (pintype "passive"))
      (node (ref "LED7") (pin "K") (pinfunction "C_K") (pintype "passive"))
      (node (ref "LED8") (pin "K") (pinfunction "C_K") (pintype "passive"))
      (node (ref "LED9") (pin "K") (pinfunction "C_K") (pintype "passive"))
      (node (ref "Q1") (pin "1") (pinfunction "E_1") (pintype "passive"))
      (node (ref "Q2") (pin "1") (pinfunction "E_1") (pintype "passive"))
      (node (ref "RESET") (pin "1") (pinfunction "S_1") (pintype "passive"))
      (node (ref "RESET") (pin "2") (pinfunction "S1_2") (pintype "passive"))
      (node (ref "U2") (pin "18") (pinfunction "GND2_18") (pintype "power_in"))
      (node (ref "U2") (pin "21") (pinfunction "GND3_21") (pintype "power_in"))
      (node (ref "U2") (pin "25") (pinfunction "AGND_25") (pintype "power_in"))
      (node (ref "U2") (pin "26") (pinfunction "TEST_26") (pintype "input"))
      (node (ref "U2") (pin "7") (pinfunction "GND1_7") (pintype "power_in"))
      (node (ref "USB") (pin "4") (pinfunction "4_4") (pintype "passive"))
      (node (ref "X2") (pin "1") (pinfunction "KL_1") (pintype "passive"))
      (node (ref "X3") (pin "1") (pinfunction "KL_1") (pintype "passive"))
      (node (ref "X4") (pin "1") (pinfunction "KL_1") (pintype "passive"))
      (node (ref "X5") (pin "1") (pinfunction "KL_1") (pintype "passive"))
      (node (ref "X6") (pin "1") (pinfunction "KL_1") (pintype "passive"))
      (node (ref "X7") (pin "1") (pinfunction "KL_1") (pintype "passive"))
    )
    (net (code "32") (name "Net-(D2-PadA)") (class "Default")
      (node (ref "D2") (pin "A") (pinfunction "A_A") (pintype "passive"))
      (node (ref "J1") (pin "3") (pinfunction "3_3") (pintype "passive"))
    )
    (net (code "33") (name "Net-(FERRITE-Pad2)") (class "Default")
      (node (ref "FERRITE") (pin "2") (pinfunction "2_2") (pintype "passive"))
      (node (ref "R35") (pin "2") (pinfunction "2_2") (pintype "passive"))
      (node (ref "R36") (pin "2") (pinfunction "2_2") (pintype "passive"))
      (node (ref "USB") (pin "S1") (pinfunction "S1_S1") (pintype "passive"))
      (node (ref "USB") (pin "S2") (pinfunction "S2_S2") (pintype "passive"))
    )
    (net (code "34") (name "Net-(IC1-AREF)") (class "Default")
      (node (ref "C1") (pin "1") (pinfunction "1_1") (pintype "passive"))
      (node (ref "IC1") (pin "21") (pinfunction "AREF_21") (pintype "passive"))
    )
    (net (code "35") (name "Net-(IC1-PC5(ADC5{slash}SCL))") (class "Default")
      (node (ref "IC1") (pin "28") (pinfunction "PC5(ADC5/SCL)_28") (pintype "bidirectional"))
      (node (ref "R44") (pin "2") (pinfunction "2_2") (pintype "passive"))
    )
    (net (code "36") (name "Net-(IC1-PD0(RXD))") (class "Default")
      (node (ref "IC1") (pin "2") (pinfunction "PD0(RXD)_2") (pintype "bidirectional"))
      (node (ref "R6") (pin "2") (pinfunction "2_2") (pintype "passive"))
    )
    (net (code "37") (name "Net-(IC1-PD1(TXD))") (class "Default")
      (node (ref "IC1") (pin "3") (pinfunction "PD1(TXD)_3") (pintype "bidirectional"))
      (node (ref "R7") (pin "2") (pinfunction "2_2") (pintype "passive"))
    )
    (net (code "38") (name "Net-(IC1-PD3(INT1))") (class "Default")
      (node (ref "IC1") (pin "5") (pinfunction "PD3(INT1)_5") (pintype "bidirectional"))
      (node (ref "R2") (pin "2") (pinfunction "2_2") (pintype "passive"))
    )
    (net (code "39") (name "Net-(IC1-PD4(XCK{slash}T0))") (class "Default")
      (node (ref "IC1") (pin "6") (pinfunction "PD4(XCK/T0)_6") (pintype "bidirectional"))
      (node (ref "R3") (pin "2") (pinfunction "2_2") (pintype "passive"))
    )
    (net (code "40") (name "Net-(IC1-PD5(T1))") (class "Default")
      (node (ref "IC1") (pin "11") (pinfunction "PD5(T1)_11") (pintype "bidirectional"))
      (node (ref "R33") (pin "2") (pinfunction "2_2") (pintype "passive"))
    )
    (net (code "41") (name "Net-(IC3-AREF)") (class "Default")
      (node (ref "C8") (pin "1") (pinfunction "1_1") (pintype "passive"))
      (node (ref "IC3") (pin "21") (pinfunction "AREF_21") (pintype "passive"))
    )
    (net (code "42") (name "Net-(IC3-PB0(ICP))") (class "Default")
      (node (ref "IC3") (pin "14") (pinfunction "PB0(ICP)_14") (pintype "bidirectional"))
      (node (ref "R9") (pin "2") (pinfunction "2_2") (pintype "passive"))
    )
    (net (code "43") (name "Net-(IC3-PB1(OC1A))") (class "Default")
      (node (ref "IC3") (pin "15") (pinfunction "PB1(OC1A)_15") (pintype "bidirectional"))
      (node (ref "R32") (pin "2") (pinfunction "2_2") (pintype "passive"))
    )
    (net (code "44") (name "Net-(IC3-PB2(SS{slash}OC1B))") (class "Default")
      (node (ref "IC3") (pin "16") (pinfunction "PB2(SS/OC1B)_16") (pintype "bidirectional"))
      (node (ref "R31") (pin "2") (pinfunction "2_2") (pintype "passive"))
    )
    (net (code "45") (name "Net-(IC3-PB3(MOSI{slash}OC2))") (class "Default")
      (node (ref "IC3") (pin "17") (pinfunction "PB3(MOSI/OC2)_17") (pintype "bidirectional"))
      (node (ref "R29") (pin "2") (pinfunction "2_2") (pintype "passive"))
    )
    (net (code "46") (name "Net-(IC3-PD0(RXD))") (class "Default")
      (node (ref "IC3") (pin "2") (pinfunction "PD0(RXD)_2") (pintype "bidirectional"))
      (node (ref "R27") (pin "2") (pinfunction "2_2") (pintype "passive"))
    )
    (net (code "47") (name "Net-(IC3-PD1(TXD))") (class "Default")
      (node (ref "IC3") (pin "3") (pinfunction "PD1(TXD)_3") (pintype "bidirectional"))
      (node (ref "R28") (pin "2") (pinfunction "2_2") (pintype "passive"))
    )
    (net (code "48") (name "Net-(IC3-PD6(AIN0))") (class "Default")
      (node (ref "IC3") (pin "12") (pinfunction "PD6(AIN0)_12") (pintype "bidirectional"))
      (node (ref "R25") (pin "2") (pinfunction "2_2") (pintype "passive"))
    )
    (net (code "49") (name "Net-(IC3-PD7(AIN1))") (class "Default")
      (node (ref "IC3") (pin "13") (pinfunction "PD7(AIN1)_13") (pintype "bidirectional"))
      (node (ref "R26") (pin "2") (pinfunction "2_2") (pintype "passive"))
    )
    (net (code "50") (name "Net-(LED1-PadA)") (class "Default")
      (node (ref "LED1") (pin "A") (pinfunction "A_A") (pintype "passive"))
      (node (ref "R9") (pin "1") (pinfunction "1_1") (pintype "passive"))
    )
    (net (code "51") (name "Net-(LED3-PadA)") (class "Default")
      (node (ref "LED3") (pin "A") (pinfunction "A_A") (pintype "passive"))
      (node (ref "R2") (pin "1") (pinfunction "1_1") (pintype "passive"))
    )
    (net (code "52") (name "Net-(LED4-PadA)") (class "Default")
      (node (ref "LED4") (pin "A") (pinfunction "A_A") (pintype "passive"))
      (node (ref "R3") (pin "1") (pinfunction "1_1") (pintype "passive"))
    )
    (net (code "53") (name "Net-(LED5-PadA)") (class "Default")
      (node (ref "LED5") (pin "A") (pinfunction "A_A") (pintype "passive"))
      (node (ref "R25") (pin "1") (pinfunction "1_1") (pintype "passive"))
    )
    (net (code "54") (name "Net-(LED6-C)") (class "Default")
      (node (ref "LED6") (pin "K") (pinfunction "C_K") (pintype "passive"))
      (node (ref "U2") (pin "23") (pinfunction "CBUS0_23") (pintype "bidirectional"))
    )
    (net (code "55") (name "Net-(LED6-PadA)") (class "Default")
      (node (ref "LED6") (pin "A") (pinfunction "A_A") (pintype "passive"))
      (node (ref "R11") (pin "1") (pinfunction "1_1") (pintype "passive"))
    )
    (net (code "56") (name "Net-(LED7-PadA)") (class "Default")
      (node (ref "LED7") (pin "A") (pinfunction "A_A") (pintype "passive"))
      (node (ref "R26") (pin "1") (pinfunction "1_1") (pintype "passive"))
    )
    (net (code "57") (name "Net-(LED8-PadA)") (class "Default")
      (node (ref "LED8") (pin "A") (pinfunction "A_A") (pintype "passive"))
      (node (ref "R29") (pin "1") (pinfunction "1_1") (pintype "passive"))
    )
    (net (code "58") (name "Net-(LED9-PadA)") (class "Default")
      (node (ref "LED9") (pin "A") (pinfunction "A_A") (pintype "passive"))
      (node (ref "R31") (pin "1") (pinfunction "1_1") (pintype "passive"))
    )
    (net (code "59") (name "Net-(LED10-PadA)") (class "Default")
      (node (ref "LED10") (pin "A") (pinfunction "A_A") (pintype "passive"))
      (node (ref "R32") (pin "1") (pinfunction "1_1") (pintype "passive"))
    )
    (net (code "60") (name "Net-(LED11-PadA)") (class "Default")
      (node (ref "LED11") (pin "A") (pinfunction "A_A") (pintype "passive"))
      (node (ref "R33") (pin "1") (pinfunction "1_1") (pintype "passive"))
    )
    (net (code "61") (name "Net-(LED12-PadA)") (class "Default")
      (node (ref "LED12") (pin "A") (pinfunction "A_A") (pintype "passive"))
      (node (ref "R34") (pin "1") (pinfunction "1_1") (pintype "passive"))
    )
    (net (code "62") (name "Net-(LED13-C)") (class "Default")
      (node (ref "LED13") (pin "K") (pinfunction "C_K") (pintype "passive"))
      (node (ref "U2") (pin "22") (pinfunction "CBUS1_22") (pintype "bidirectional"))
    )
    (net (code "63") (name "Net-(LED13-PadA)") (class "Default")
      (node (ref "LED13") (pin "A") (pinfunction "A_A") (pintype "passive"))
      (node (ref "R37") (pin "1") (pinfunction "1_1") (pintype "passive"))
    )
    (net (code "64") (name "Net-(OK1A-A)") (class "Default")
      (node (ref "OK1") (pin "1") (pinfunction "A_1") (pintype "passive"))
      (node (ref "R4") (pin "1") (pinfunction "1_1") (pintype "passive"))
    )
    (net (code "65") (name "Net-(OK1A-C)") (class "Default")
      (node (ref "OK1") (pin "2") (pinfunction "C_2") (pintype "passive"))
      (node (ref "OK1") (pin "4") (pinfunction "C_4") (pintype "passive"))
      (node (ref "OK1") (pin "6") (pinfunction "C_6") (pintype "passive"))
      (node (ref "OK1") (pin "8") (pinfunction "C_8") (pintype "passive"))
      (node (ref "OK2") (pin "2") (pinfunction "C_2") (pintype "passive"))
      (node (ref "OK2") (pin "4") (pinfunction "C_4") (pintype "passive"))
      (node (ref "OK2") (pin "6") (pinfunction "C_6") (pintype "passive"))
      (node (ref "OK2") (pin "8") (pinfunction "C_8") (pintype "passive"))
      (node (ref "Q1") (pin "3") (pinfunction "C_3") (pintype "passive"))
    )
    (net (code "66") (name "Net-(OK1A-COL)") (class "Default")
      (node (ref "OK1") (pin "16") (pinfunction "COL_16") (pintype "passive"))
      (node (ref "R18") (pin "2") (pinfunction "2_2") (pintype "passive"))
      (node (ref "SV2") (pin "1") (pinfunction "1_1") (pintype "passive"))
    )
    (net (code "67") (name "Net-(OK1B-A)") (class "Default")
      (node (ref "OK1") (pin "3") (pinfunction "A_3") (pintype "passive"))
      (node (ref "R5") (pin "1") (pinfunction "1_1") (pintype "passive"))
    )
    (net (code "68") (name "Net-(OK1B-COL)") (class "Default")
      (node (ref "OK1") (pin "14") (pinfunction "COL_14") (pintype "passive"))
      (node (ref "R19") (pin "2") (pinfunction "2_2") (pintype "passive"))
      (node (ref "SV2") (pin "3") (pinfunction "3_3") (pintype "passive"))
    )
    (net (code "69") (name "Net-(OK1C-A)") (class "Default")
      (node (ref "OK1") (pin "5") (pinfunction "A_5") (pintype "passive"))
      (node (ref "R12") (pin "1") (pinfunction "1_1") (pintype "passive"))
    )
    (net (code "70") (name "Net-(OK1C-COL)") (class "Default")
      (node (ref "OK1") (pin "12") (pinfunction "COL_12") (pintype "passive"))
      (node (ref "R20") (pin "2") (pinfunction "2_2") (pintype "passive"))
      (node (ref "SV2") (pin "5") (pinfunction "5_5") (pintype "passive"))
    )
    (net (code "71") (name "Net-(OK1D-A)") (class "Default")
      (node (ref "OK1") (pin "7") (pinfunction "A_7") (pintype "passive"))
      (node (ref "R13") (pin "1") (pinfunction "1_1") (pintype "passive"))
    )
    (net (code "72") (name "Net-(OK1D-COL)") (class "Default")
      (node (ref "OK1") (pin "10") (pinfunction "COL_10") (pintype "passive"))
      (node (ref "R21") (pin "2") (pinfunction "2_2") (pintype "passive"))
      (node (ref "SV2") (pin "7") (pinfunction "7_7") (pintype "passive"))
    )
    (net (code "73") (name "Net-(OK2A-A)") (class "Default")
      (node (ref "OK2") (pin "1") (pinfunction "A_1") (pintype "passive"))
      (node (ref "R14") (pin "1") (pinfunction "1_1") (pintype "passive"))
    )
    (net (code "74") (name "Net-(OK2A-COL)") (class "Default")
      (node (ref "OK2") (pin "16") (pinfunction "COL_16") (pintype "passive"))
      (node (ref "R22") (pin "2") (pinfunction "2_2") (pintype "passive"))
      (node (ref "SV2") (pin "9") (pinfunction "9_9") (pintype "passive"))
    )
    (net (code "75") (name "Net-(OK2B-A)") (class "Default")
      (node (ref "OK2") (pin "3") (pinfunction "A_3") (pintype "passive"))
      (node (ref "R15") (pin "1") (pinfunction "1_1") (pintype "passive"))
    )
    (net (code "76") (name "Net-(OK2B-COL)") (class "Default")
      (node (ref "OK2") (pin "14") (pinfunction "COL_14") (pintype "passive"))
      (node (ref "R23") (pin "2") (pinfunction "2_2") (pintype "passive"))
      (node (ref "SV2") (pin "11") (pinfunction "11_11") (pintype "passive"))
    )
    (net (code "77") (name "Net-(OK2C-A)") (class "Default")
      (node (ref "OK2") (pin "5") (pinfunction "A_5") (pintype "passive"))
      (node (ref "R16") (pin "1") (pinfunction "1_1") (pintype "passive"))
    )
    (net (code "78") (name "Net-(OK2D-A)") (class "Default")
      (node (ref "OK2") (pin "7") (pinfunction "A_7") (pintype "passive"))
      (node (ref "R45") (pin "1") (pinfunction "1_1") (pintype "passive"))
    )
    (net (code "79") (name "Net-(Q1-B)") (class "Default")
      (node (ref "Q1") (pin "2") (pinfunction "B_2") (pintype "passive"))
      (node (ref "R38") (pin "1") (pinfunction "1_1") (pintype "passive"))
    )
    (net (code "80") (name "Net-(Q2-B)") (class "Default")
      (node (ref "Q2") (pin "2") (pinfunction "B_2") (pintype "passive"))
      (node (ref "R44") (pin "1") (pinfunction "1_1") (pintype "passive"))
    )
    (net (code "81") (name "Net-(U2-3V3OUT)") (class "Default")
      (node (ref "C7") (pin "2") (pinfunction "2_2") (pintype "passive"))
      (node (ref "U2") (pin "17") (pinfunction "3V3OUT_17") (pintype "output"))
    )
    (net (code "82") (name "unconnected-(H1-MOUNT-PadB3,0)") (class "Default")
      (node (ref "H1") (pin "B3,0") (pinfunction "MOUNT_B3,0") (pintype "passive"))
    )
    (net (code "83") (name "unconnected-(H2-MOUNT-PadB3,0)") (class "Default")
      (node (ref "H2") (pin "B3,0") (pinfunction "MOUNT_B3,0") (pintype "passive"))
    )
    (net (code "84") (name "unconnected-(H3-MOUNT-PadB3,0)") (class "Default")
      (node (ref "H3") (pin "B3,0") (pinfunction "MOUNT_B3,0") (pintype "passive"))
    )
    (net (code "85") (name "unconnected-(H4-MOUNT-PadB3,0)") (class "Default")
      (node (ref "H4") (pin "B3,0") (pinfunction "MOUNT_B3,0") (pintype "passive"))
    )
    (net (code "86") (name "unconnected-(IC1-PB6(XTAL1{slash}TOSC1)-Pad9)") (class "Default")
      (node (ref "IC1") (pin "9") (pinfunction "PB6(XTAL1/TOSC1)_9") (pintype "bidirectional"))
    )
    (net (code "87") (name "unconnected-(IC1-PB7(XTAL2{slash}TOSC2)-Pad10)") (class "Default")
      (node (ref "IC1") (pin "10") (pinfunction "PB7(XTAL2/TOSC2)_10") (pintype "bidirectional"))
    )
    (net (code "88") (name "unconnected-(IC1-PC0(ADC0)-Pad23)") (class "Default")
      (node (ref "IC1") (pin "23") (pinfunction "PC0(ADC0)_23") (pintype "bidirectional"))
    )
    (net (code "89") (name "unconnected-(IC1-PC1(ADC1)-Pad24)") (class "Default")
      (node (ref "IC1") (pin "24") (pinfunction "PC1(ADC1)_24") (pintype "bidirectional"))
    )
    (net (code "90") (name "unconnected-(IC1-PC2(ADC2)-Pad25)") (class "Default")
      (node (ref "IC1") (pin "25") (pinfunction "PC2(ADC2)_25") (pintype "bidirectional"))
    )
    (net (code "91") (name "unconnected-(IC1-PC3(ADC3)-Pad26)") (class "Default")
      (node (ref "IC1") (pin "26") (pinfunction "PC3(ADC3)_26") (pintype "bidirectional"))
    )
    (net (code "92") (name "unconnected-(IC1-PC4(ADC4{slash}SDA)-Pad27)") (class "Default")
      (node (ref "IC1") (pin "27") (pinfunction "PC4(ADC4/SDA)_27") (pintype "bidirectional"))
    )
    (net (code "93") (name "unconnected-(IC1-PD2(INT0)-Pad4)") (class "Default")
      (node (ref "IC1") (pin "4") (pinfunction "PD2(INT0)_4") (pintype "bidirectional"))
    )
    (net (code "94") (name "unconnected-(IC3-PB6(XTAL1{slash}TOSC1)-Pad9)") (class "Default")
      (node (ref "IC3") (pin "9") (pinfunction "PB6(XTAL1/TOSC1)_9") (pintype "bidirectional"))
    )
    (net (code "95") (name "unconnected-(IC3-PB7(XTAL2{slash}TOSC2)-Pad10)") (class "Default")
      (node (ref "IC3") (pin "10") (pinfunction "PB7(XTAL2/TOSC2)_10") (pintype "bidirectional"))
    )
    (net (code "96") (name "unconnected-(IC3-PC0(ADC0)-Pad23)") (class "Default")
      (node (ref "IC3") (pin "23") (pinfunction "PC0(ADC0)_23") (pintype "bidirectional"))
    )
    (net (code "97") (name "unconnected-(IC3-PC1(ADC1)-Pad24)") (class "Default")
      (node (ref "IC3") (pin "24") (pinfunction "PC1(ADC1)_24") (pintype "bidirectional"))
    )
    (net (code "98") (name "unconnected-(IC3-PC2(ADC2)-Pad25)") (class "Default")
      (node (ref "IC3") (pin "25") (pinfunction "PC2(ADC2)_25") (pintype "bidirectional"))
    )
    (net (code "99") (name "unconnected-(SV2-Pad2)") (class "Default")
      (node (ref "SV2") (pin "2") (pinfunction "2_2") (pintype "passive"))
    )
    (net (code "100") (name "unconnected-(SV2-Pad12)") (class "Default")
      (node (ref "SV2") (pin "12") (pinfunction "12_12") (pintype "passive"))
    )
    (net (code "101") (name "unconnected-(SV2-Pad13)") (class "Default")
      (node (ref "SV2") (pin "13") (pinfunction "13_13") (pintype "passive"))
    )
    (net (code "102") (name "unconnected-(SV2-Pad14)") (class "Default")
      (node (ref "SV2") (pin "14") (pinfunction "14_14") (pintype "passive"))
    )
    (net (code "103") (name "unconnected-(SV2-Pad15)") (class "Default")
      (node (ref "SV2") (pin "15") (pinfunction "15_15") (pintype "passive"))
    )
    (net (code "104") (name "unconnected-(SV2-Pad16)") (class "Default")
      (node (ref "SV2") (pin "16") (pinfunction "16_16") (pintype "passive"))
    )
    (net (code "105") (name "unconnected-(U2-CBUS2-Pad13)") (class "Default")
      (node (ref "U2") (pin "13") (pinfunction "CBUS2_13") (pintype "bidirectional"))
    )
    (net (code "106") (name "unconnected-(U2-CBUS3-Pad14)") (class "Default")
      (node (ref "U2") (pin "14") (pinfunction "CBUS3_14") (pintype "bidirectional"))
    )
    (net (code "107") (name "unconnected-(U2-CBUS4-Pad12)") (class "Default")
      (node (ref "U2") (pin "12") (pinfunction "CBUS4_12") (pintype "bidirectional"))
    )
    (net (code "108") (name "unconnected-(U2-CTS#-Pad11)") (class "Default")
      (node (ref "U2") (pin "11") (pinfunction "CTS#_11") (pintype "input"))
    )
    (net (code "109") (name "unconnected-(U2-DCD#-Pad10)") (class "Default")
      (node (ref "U2") (pin "10") (pinfunction "DCD#_10") (pintype "input"))
    )
    (net (code "110") (name "unconnected-(U2-DSR#-Pad9)") (class "Default")
      (node (ref "U2") (pin "9") (pinfunction "DSR#_9") (pintype "input"))
    )
    (net (code "111") (name "unconnected-(U2-DTR#-Pad2)") (class "Default")
      (node (ref "U2") (pin "2") (pinfunction "DTR#_2") (pintype "output"))
    )
    (net (code "112") (name "unconnected-(U2-OSCI-Pad27)") (class "Default")
      (node (ref "U2") (pin "27") (pinfunction "OSCI_27") (pintype "input"))
    )
    (net (code "113") (name "unconnected-(U2-OSCO-Pad28)") (class "Default")
      (node (ref "U2") (pin "28") (pinfunction "OSCO_28") (pintype "output"))
    )
    (net (code "114") (name "unconnected-(U2-RI#-Pad6)") (class "Default")
      (node (ref "U2") (pin "6") (pinfunction "RI#_6") (pintype "input"))
    )
    (net (code "115") (name "unconnected-(U2-RTS#-Pad3)") (class "Default")
      (node (ref "U2") (pin "3") (pinfunction "RTS#_3") (pintype "output"))
    )
    (net (code "116") (name "unconnected-(USB-Pad1)") (class "Default")
      (node (ref "USB") (pin "1") (pinfunction "1_1") (pintype "passive"))
    )
  )
)
